# design.net
KiCad netlist of a schematic drawn in Altium Designer
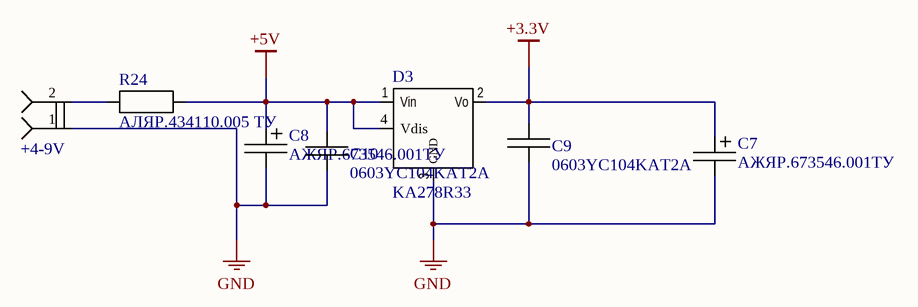
[diagram p0: Питание.SchDoc]

(export (version "E")
  (design (tool "Eeschema 10.0.6"))
  (components
    (comp (ref "+4-9V")
      (value "~")
      (footprint "284392-2_TE")
      (fields
        (field (name "MANUFACTURER") "Tyco Electronics")
        (field (name "MANUFACTURERPARTNUMBER") "284392-2")
      )
      (libsource (lib "РАЗЪЕМЫ") (part "Клемник 3.81х2 TE"))
    )
    (comp (ref "C7")
      (value "АЖЯР.673546.001ТУ")
      (footprint "К53-56_ТИП5")
      (fields
        (field (name "MANUFACTURERPARTNUMBER") "ОСМ К53-56А-16В-100 мкФ ±10% -АЖЯР.673546.001ТУ П0.070.052")
        (field (name "TOLERANCE") "±10%")
      )
      (libsource (lib "КОНДЕНСАТОРЫ") (part "ОСМ К53-56А-16В-100"))
    )
    (comp (ref "C8")
      (value "АЖЯР.673546.001ТУ")
      (footprint "К53-56_ТИП5")
      (fields
        (field (name "MANUFACTURERPARTNUMBER") "ОСМ К53-56А-16В-100 мкФ ±10% -АЖЯР.673546.001ТУ П0.070.052")
        (field (name "TOLERANCE") "±10%")
      )
      (libsource (lib "КОНДЕНСАТОРЫ") (part "ОСМ К53-56А-16В-100"))
    )
    (comp (ref "C9")
      (value "0603YC104KAT2A")
      (footprint "0603-AVX")
      (fields (field (name "MANUFACTURER") "AVX") (field (name "TOLERANCE") "±10%"))
      (libsource (lib "КОНДЕНСАТОРЫ") (part "0603-X7R-0,1мкФ-16В-10%"))
    )
    (comp (ref "C10")
      (value "0603YC104KAT2A")
      (footprint "0603-AVX")
      (fields (field (name "MANUFACTURER") "AVX") (field (name "TOLERANCE") "±10%"))
      (libsource (lib "КОНДЕНСАТОРЫ") (part "0603-X7R-0,1мкФ-16В-10%"))
    )
    (comp (ref "D3")
      (value "KA278R33")
      (footprint "TO220-F-4L")
      (fields (field (name "MANUFACTURERPARTNUMBER") "LM317MQDCYR"))
      (libsource (lib "МИКРОСХЕМЫ") (part "KA278R33"))
    )
    (comp (ref "R24")
      (value "АЛЯР.434110.005 ТУ")
      (footprint "Р1-12-0,25")
      (fields
        (field (name "TOLERANCE") "±5%")
        (field (name "MANUFACTURERPARTNUMBER") "Р1-12-0,25-0,75 Ом±5%-У")
      )
      (libsource (lib "РЕЗИСТОРЫ") (part "Р1-12-0,25-0,75 Ом±5%"))
    )
  )
  (nets
    (net (code "1") (name "+3.3V") (class "Default")
      (node (ref "C7") (pin "1") (pinfunction "1_1") (pintype "passive"))
      (node (ref "C9") (pin "2") (pinfunction "2_2") (pintype "passive"))
      (node (ref "D3") (pin "2") (pinfunction "Vo_2") (pintype "power_in"))
    )
    (net (code "2") (name "+5V") (class "Default")
      (node (ref "C10") (pin "2") (pinfunction "2_2") (pintype "passive"))
      (node (ref "C8") (pin "1") (pinfunction "1_1") (pintype "passive"))
      (node (ref "D3") (pin "1") (pinfunction "Vin_1") (pintype "power_in"))
      (node (ref "D3") (pin "4") (pinfunction "Vdis_4") (pintype "passive"))
      (node (ref "R24") (pin "2") (pinfunction "2_2") (pintype "passive"))
    )
    (net (code "3") (name "GND") (class "Default")
      (node (ref "+4-9V") (pin "1") (pinfunction "1_1") (pintype "passive"))
      (node (ref "C10") (pin "1") (pinfunction "1_1") (pintype "passive"))
      (node (ref "C7") (pin "2") (pinfunction "2_2") (pintype "passive"))
      (node (ref "C8") (pin "2") (pinfunction "2_2") (pintype "passive"))
      (node (ref "C9") (pin "1") (pinfunction "1_1") (pintype "passive"))
      (node (ref "D3") (pin "3") (pinfunction "GND_3") (pintype "power_in"))
    )
    (net (code "4") (name "Net-(+4-9V-Pad2)") (class "Default")
      (node (ref "+4-9V") (pin "2") (pinfunction "2_2") (pintype "passive"))
      (node (ref "R24") (pin "1") (pinfunction "1_1") (pintype "passive"))
    )
  )
)
